# attenuverter3.net
KiCad netlist of a schematic drawn in EAGLE
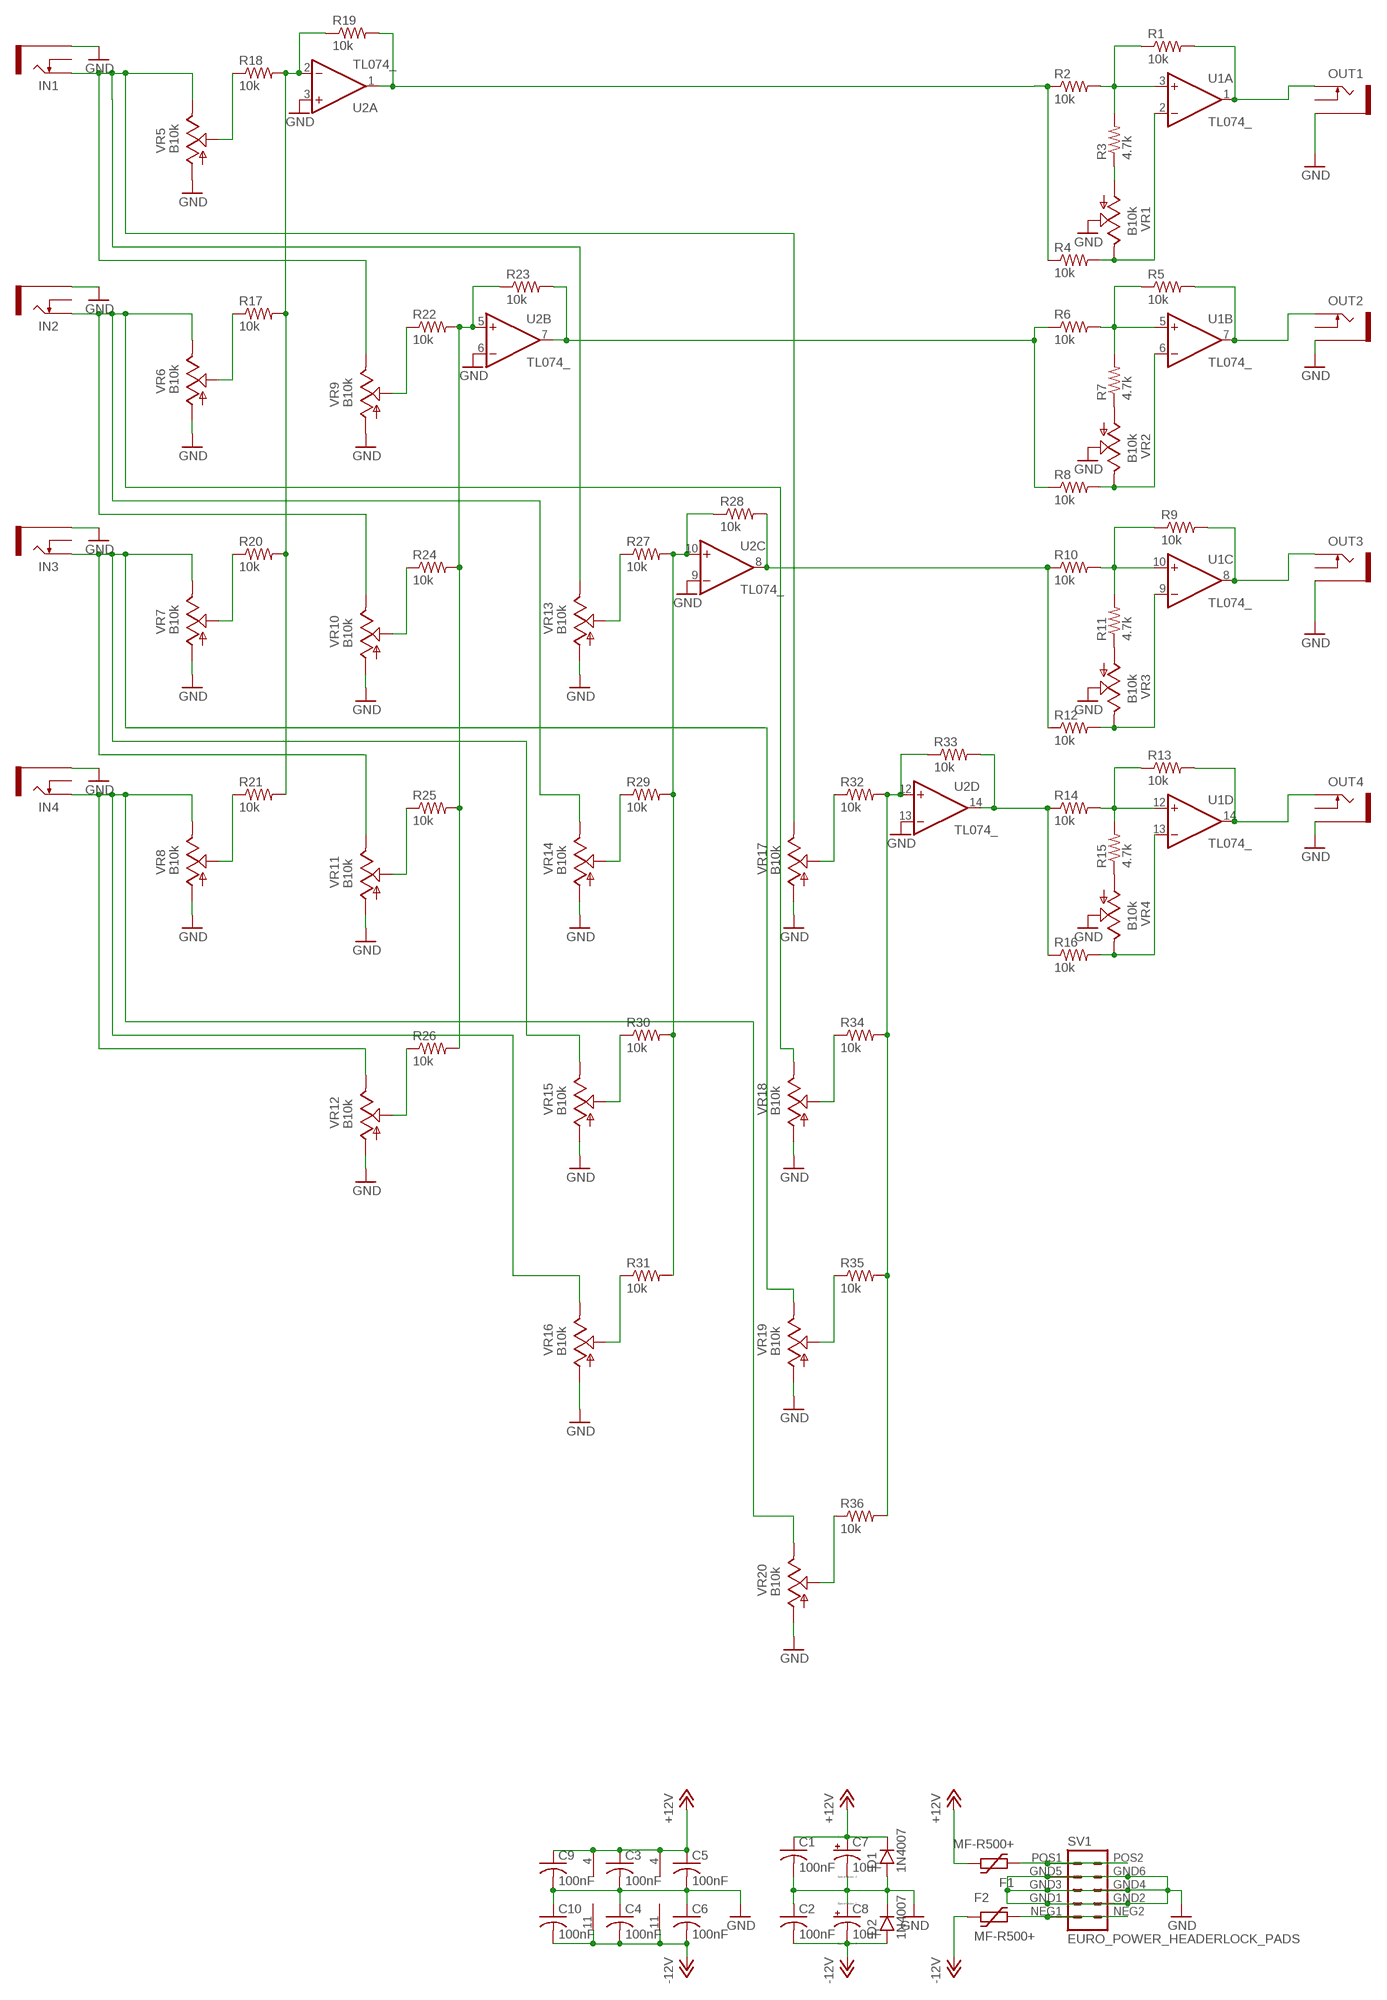
[diagram p0: schematic, sheet 1]

(export (version "E")
  (design (tool "Eeschema 10.0.6"))
  (components
    (comp (ref "C1")
      (value "100nF")
      (footprint "eagle-import:C050-055X075")
      (libsource (lib "eagle-import") (part "C-US050-055X075"))
    )
    (comp (ref "C2")
      (value "100nF")
      (footprint "eagle-import:C050-055X075")
      (libsource (lib "eagle-import") (part "C-US050-055X075"))
    )
    (comp (ref "C3")
      (value "100nF")
      (footprint "eagle-import:C050-055X075")
      (libsource (lib "eagle-import") (part "C-US050-055X075"))
    )
    (comp (ref "C4")
      (value "100nF")
      (footprint "eagle-import:C050-055X075")
      (libsource (lib "eagle-import") (part "C-US050-055X075"))
    )
    (comp (ref "C5")
      (value "100nF")
      (footprint "eagle-import:C050-055X075")
      (libsource (lib "eagle-import") (part "C-US050-055X075"))
    )
    (comp (ref "C6")
      (value "100nF")
      (footprint "eagle-import:C050-055X075")
      (libsource (lib "eagle-import") (part "C-US050-055X075"))
    )
    (comp (ref "C7")
      (value "10uF")
      (footprint "eagle-import:E2,5-6")
      (libsource (lib "eagle-import") (part "CPOL-USE2.5-6"))
    )
    (comp (ref "C8")
      (value "10uF")
      (footprint "eagle-import:E2,5-6")
      (libsource (lib "eagle-import") (part "CPOL-USE2.5-6"))
    )
    (comp (ref "C9")
      (value "100nF")
      (footprint "eagle-import:C050-055X075")
      (libsource (lib "eagle-import") (part "C-US050-055X075"))
    )
    (comp (ref "C10")
      (value "100nF")
      (footprint "eagle-import:C050-055X075")
      (libsource (lib "eagle-import") (part "C-US050-055X075"))
    )
    (comp (ref "D1")
      (value "1N4007")
      (footprint "eagle-import:DO41-4")
      (libsource (lib "eagle-import") (part "1N400X.4"))
    )
    (comp (ref "D2")
      (value "1N4007")
      (footprint "eagle-import:DO41-4")
      (libsource (lib "eagle-import") (part "1N400X.4"))
    )
    (comp (ref "F1")
      (value "MF-R500+")
      (footprint "eagle-import:BOURNS-MF-R")
      (libsource (lib "eagle-import") (part "MF-R500+"))
    )
    (comp (ref "F2")
      (value "MF-R500+")
      (footprint "eagle-import:BOURNS-MF-R")
      (libsource (lib "eagle-import") (part "MF-R500+"))
    )
    (comp (ref "IN1")
      (value "THONKICONNNEW")
      (footprint "eagle-import:WQP-PJ301M-12_JACK")
      (libsource (lib "eagle-import") (part "THONKICONNNEW"))
    )
    (comp (ref "IN2")
      (value "THONKICONNNEW")
      (footprint "eagle-import:WQP-PJ301M-12_JACK")
      (libsource (lib "eagle-import") (part "THONKICONNNEW"))
    )
    (comp (ref "IN3")
      (value "THONKICONNNEW")
      (footprint "eagle-import:WQP-PJ301M-12_JACK")
      (libsource (lib "eagle-import") (part "THONKICONNNEW"))
    )
    (comp (ref "IN4")
      (value "THONKICONNNEW")
      (footprint "eagle-import:WQP-PJ301M-12_JACK")
      (libsource (lib "eagle-import") (part "THONKICONNNEW"))
    )
    (comp (ref "OUT1")
      (value "THONKICONNNEW")
      (footprint "eagle-import:WQP-PJ301M-12_JACK")
      (libsource (lib "eagle-import") (part "THONKICONNNEW"))
    )
    (comp (ref "OUT2")
      (value "THONKICONNNEW")
      (footprint "eagle-import:WQP-PJ301M-12_JACK")
      (libsource (lib "eagle-import") (part "THONKICONNNEW"))
    )
    (comp (ref "OUT3")
      (value "THONKICONNNEW")
      (footprint "eagle-import:WQP-PJ301M-12_JACK")
      (libsource (lib "eagle-import") (part "THONKICONNNEW"))
    )
    (comp (ref "OUT4")
      (value "THONKICONNNEW")
      (footprint "eagle-import:WQP-PJ301M-12_JACK")
      (libsource (lib "eagle-import") (part "THONKICONNNEW"))
    )
    (comp (ref "R1")
      (value "10k")
      (footprint "eagle-import:0207_7")
      (libsource (lib "eagle-import") (part "R-US_0207/7"))
    )
    (comp (ref "R2")
      (value "10k")
      (footprint "eagle-import:0207_7")
      (libsource (lib "eagle-import") (part "R-US_0207/7"))
    )
    (comp (ref "R3")
      (value "4.7k")
      (footprint "eagle-import:0207_7")
      (libsource (lib "eagle-import") (part "R-US_0207/7"))
    )
    (comp (ref "R4")
      (value "10k")
      (footprint "eagle-import:0207_7")
      (libsource (lib "eagle-import") (part "R-US_0207/7"))
    )
    (comp (ref "R5")
      (value "10k")
      (footprint "eagle-import:0207_7")
      (libsource (lib "eagle-import") (part "R-US_0207/7"))
    )
    (comp (ref "R6")
      (value "10k")
      (footprint "eagle-import:0207_7")
      (libsource (lib "eagle-import") (part "R-US_0207/7"))
    )
    (comp (ref "R7")
      (value "4.7k")
      (footprint "eagle-import:0207_7")
      (libsource (lib "eagle-import") (part "R-US_0207/7"))
    )
    (comp (ref "R8")
      (value "10k")
      (footprint "eagle-import:0207_7")
      (libsource (lib "eagle-import") (part "R-US_0207/7"))
    )
    (comp (ref "R9")
      (value "10k")
      (footprint "eagle-import:0207_7")
      (libsource (lib "eagle-import") (part "R-US_0207/7"))
    )
    (comp (ref "R10")
      (value "10k")
      (footprint "eagle-import:0207_7")
      (libsource (lib "eagle-import") (part "R-US_0207/7"))
    )
    (comp (ref "R11")
      (value "4.7k")
      (footprint "eagle-import:0207_7")
      (libsource (lib "eagle-import") (part "R-US_0207/7"))
    )
    (comp (ref "R12")
      (value "10k")
      (footprint "eagle-import:0207_7")
      (libsource (lib "eagle-import") (part "R-US_0207/7"))
    )
    (comp (ref "R13")
      (value "10k")
      (footprint "eagle-import:0207_7")
      (libsource (lib "eagle-import") (part "R-US_0207/7"))
    )
    (comp (ref "R14")
      (value "10k")
      (footprint "eagle-import:0207_7")
      (libsource (lib "eagle-import") (part "R-US_0207/7"))
    )
    (comp (ref "R15")
      (value "4.7k")
      (footprint "eagle-import:0207_7")
      (libsource (lib "eagle-import") (part "R-US_0207/7"))
    )
    (comp (ref "R16")
      (value "10k")
      (footprint "eagle-import:0207_7")
      (libsource (lib "eagle-import") (part "R-US_0207/7"))
    )
    (comp (ref "R17")
      (value "10k")
      (footprint "eagle-import:0207_7")
      (libsource (lib "eagle-import") (part "R-US_0207/7"))
    )
    (comp (ref "R18")
      (value "10k")
      (footprint "eagle-import:0207_7")
      (libsource (lib "eagle-import") (part "R-US_0207/7"))
    )
    (comp (ref "R19")
      (value "10k")
      (footprint "eagle-import:0207_7")
      (libsource (lib "eagle-import") (part "R-US_0207/7"))
    )
    (comp (ref "R20")
      (value "10k")
      (footprint "eagle-import:0207_7")
      (libsource (lib "eagle-import") (part "R-US_0207/7"))
    )
    (comp (ref "R21")
      (value "10k")
      (footprint "eagle-import:0207_7")
      (libsource (lib "eagle-import") (part "R-US_0207/7"))
    )
    (comp (ref "R22")
      (value "10k")
      (footprint "eagle-import:0207_7")
      (libsource (lib "eagle-import") (part "R-US_0207/7"))
    )
    (comp (ref "R23")
      (value "10k")
      (footprint "eagle-import:0207_7")
      (libsource (lib "eagle-import") (part "R-US_0207/7"))
    )
    (comp (ref "R24")
      (value "10k")
      (footprint "eagle-import:0207_7")
      (libsource (lib "eagle-import") (part "R-US_0207/7"))
    )
    (comp (ref "R25")
      (value "10k")
      (footprint "eagle-import:0207_7")
      (libsource (lib "eagle-import") (part "R-US_0207/7"))
    )
    (comp (ref "R26")
      (value "10k")
      (footprint "eagle-import:0207_7")
      (libsource (lib "eagle-import") (part "R-US_0207/7"))
    )
    (comp (ref "R27")
      (value "10k")
      (footprint "eagle-import:0207_7")
      (libsource (lib "eagle-import") (part "R-US_0207/7"))
    )
    (comp (ref "R28")
      (value "10k")
      (footprint "eagle-import:0207_7")
      (libsource (lib "eagle-import") (part "R-US_0207/7"))
    )
    (comp (ref "R29")
      (value "10k")
      (footprint "eagle-import:0207_7")
      (libsource (lib "eagle-import") (part "R-US_0207/7"))
    )
    (comp (ref "R30")
      (value "10k")
      (footprint "eagle-import:0207_7")
      (libsource (lib "eagle-import") (part "R-US_0207/7"))
    )
    (comp (ref "R31")
      (value "10k")
      (footprint "eagle-import:0207_7")
      (libsource (lib "eagle-import") (part "R-US_0207/7"))
    )
    (comp (ref "R32")
      (value "10k")
      (footprint "eagle-import:0207_7")
      (libsource (lib "eagle-import") (part "R-US_0207/7"))
    )
    (comp (ref "R33")
      (value "10k")
      (footprint "eagle-import:0207_7")
      (libsource (lib "eagle-import") (part "R-US_0207/7"))
    )
    (comp (ref "R34")
      (value "10k")
      (footprint "eagle-import:0207_7")
      (libsource (lib "eagle-import") (part "R-US_0207/7"))
    )
    (comp (ref "R35")
      (value "10k")
      (footprint "eagle-import:0207_7")
      (libsource (lib "eagle-import") (part "R-US_0207/7"))
    )
    (comp (ref "R36")
      (value "10k")
      (footprint "eagle-import:0207_7")
      (libsource (lib "eagle-import") (part "R-US_0207/7"))
    )
    (comp (ref "SV1")
      (value "EURO_POWER_HEADERLOCK_PADS")
      (footprint "eagle-import:EURO_PWR_HEADER_LOCK")
      (libsource (lib "eagle-import") (part "EURO_POWER_HEADERLOCK_PADS"))
    )
    (comp (ref "U1")
      (value "TL074_")
      (footprint "eagle-import:DIL14")
      (libsource (lib "eagle-import") (part "TL074_"))
    )
    (comp (ref "U2")
      (value "TL074_")
      (footprint "eagle-import:DIL14")
      (libsource (lib "eagle-import") (part "TL074_"))
    )
    (comp (ref "VR1")
      (value "B10k")
      (footprint "eagle-import:9MM_SNAP-IN_POT")
      (libsource (lib "eagle-import") (part "9MM_SNAP-IN_POT_"))
    )
    (comp (ref "VR2")
      (value "B10k")
      (footprint "eagle-import:9MM_SNAP-IN_POT")
      (libsource (lib "eagle-import") (part "9MM_SNAP-IN_POT_"))
    )
    (comp (ref "VR3")
      (value "B10k")
      (footprint "eagle-import:9MM_SNAP-IN_POT")
      (libsource (lib "eagle-import") (part "9MM_SNAP-IN_POT_"))
    )
    (comp (ref "VR4")
      (value "B10k")
      (footprint "eagle-import:9MM_SNAP-IN_POT")
      (libsource (lib "eagle-import") (part "9MM_SNAP-IN_POT_"))
    )
    (comp (ref "VR5")
      (value "B10k")
      (footprint "eagle-import:9MM_SNAP-IN_POT")
      (libsource (lib "eagle-import") (part "9MM_SNAP-IN_POT_"))
    )
    (comp (ref "VR6")
      (value "B10k")
      (footprint "eagle-import:9MM_SNAP-IN_POT")
      (libsource (lib "eagle-import") (part "9MM_SNAP-IN_POT_"))
    )
    (comp (ref "VR7")
      (value "B10k")
      (footprint "eagle-import:9MM_SNAP-IN_POT")
      (libsource (lib "eagle-import") (part "9MM_SNAP-IN_POT_"))
    )
    (comp (ref "VR8")
      (value "B10k")
      (footprint "eagle-import:9MM_SNAP-IN_POT")
      (libsource (lib "eagle-import") (part "9MM_SNAP-IN_POT_"))
    )
    (comp (ref "VR9")
      (value "B10k")
      (footprint "eagle-import:9MM_SNAP-IN_POT")
      (libsource (lib "eagle-import") (part "9MM_SNAP-IN_POT_"))
    )
    (comp (ref "VR10")
      (value "B10k")
      (footprint "eagle-import:9MM_SNAP-IN_POT")
      (libsource (lib "eagle-import") (part "9MM_SNAP-IN_POT_"))
    )
    (comp (ref "VR11")
      (value "B10k")
      (footprint "eagle-import:9MM_SNAP-IN_POT")
      (libsource (lib "eagle-import") (part "9MM_SNAP-IN_POT_"))
    )
    (comp (ref "VR12")
      (value "B10k")
      (footprint "eagle-import:9MM_SNAP-IN_POT")
      (libsource (lib "eagle-import") (part "9MM_SNAP-IN_POT_"))
    )
    (comp (ref "VR13")
      (value "B10k")
      (footprint "eagle-import:9MM_SNAP-IN_POT")
      (libsource (lib "eagle-import") (part "9MM_SNAP-IN_POT_"))
    )
    (comp (ref "VR14")
      (value "B10k")
      (footprint "eagle-import:9MM_SNAP-IN_POT")
      (libsource (lib "eagle-import") (part "9MM_SNAP-IN_POT_"))
    )
    (comp (ref "VR15")
      (value "B10k")
      (footprint "eagle-import:9MM_SNAP-IN_POT")
      (libsource (lib "eagle-import") (part "9MM_SNAP-IN_POT_"))
    )
    (comp (ref "VR16")
      (value "B10k")
      (footprint "eagle-import:9MM_SNAP-IN_POT")
      (libsource (lib "eagle-import") (part "9MM_SNAP-IN_POT_"))
    )
    (comp (ref "VR17")
      (value "B10k")
      (footprint "eagle-import:9MM_SNAP-IN_POT")
      (libsource (lib "eagle-import") (part "9MM_SNAP-IN_POT_"))
    )
    (comp (ref "VR18")
      (value "B10k")
      (footprint "eagle-import:9MM_SNAP-IN_POT")
      (libsource (lib "eagle-import") (part "9MM_SNAP-IN_POT_"))
    )
    (comp (ref "VR19")
      (value "B10k")
      (footprint "eagle-import:9MM_SNAP-IN_POT")
      (libsource (lib "eagle-import") (part "9MM_SNAP-IN_POT_"))
    )
    (comp (ref "VR20")
      (value "B10k")
      (footprint "eagle-import:9MM_SNAP-IN_POT")
      (libsource (lib "eagle-import") (part "9MM_SNAP-IN_POT_"))
    )
  )
  (nets
    (net (code "1") (name "+12V") (class "Default")
      (node (ref "C1") (pin "1") (pinfunction "1_1") (pintype "passive"))
      (node (ref "C3") (pin "1") (pinfunction "1_1") (pintype "passive"))
      (node (ref "C5") (pin "1") (pinfunction "1_1") (pintype "passive"))
      (node (ref "C7") (pin "+") (pinfunction "+_+") (pintype "passive"))
      (node (ref "C9") (pin "1") (pinfunction "1_1") (pintype "passive"))
      (node (ref "D1") (pin "C") (pinfunction "C_C") (pintype "passive"))
      (node (ref "F1") (pin "P$2") (pinfunction "2_P$2") (pintype "passive"))
      (node (ref "U1") (pin "4") (pinfunction "V+_4") (pintype "power_in"))
      (node (ref "U2") (pin "4") (pinfunction "V+_4") (pintype "power_in"))
    )
    (net (code "2") (name "-12V") (class "Default")
      (node (ref "C10") (pin "2") (pinfunction "2_2") (pintype "passive"))
      (node (ref "C2") (pin "2") (pinfunction "2_2") (pintype "passive"))
      (node (ref "C4") (pin "2") (pinfunction "2_2") (pintype "passive"))
      (node (ref "C6") (pin "2") (pinfunction "2_2") (pintype "passive"))
      (node (ref "C8") (pin "-") (pinfunction "-_-") (pintype "passive"))
      (node (ref "D2") (pin "A") (pinfunction "A_A") (pintype "passive"))
      (node (ref "F2") (pin "P$1") (pinfunction "1_P$1") (pintype "passive"))
      (node (ref "U1") (pin "11") (pinfunction "V-_11") (pintype "power_in"))
      (node (ref "U2") (pin "11") (pinfunction "V-_11") (pintype "power_in"))
    )
    (net (code "3") (name "GND") (class "Default")
      (node (ref "C1") (pin "2") (pinfunction "2_2") (pintype "passive"))
      (node (ref "C10") (pin "1") (pinfunction "1_1") (pintype "passive"))
      (node (ref "C2") (pin "1") (pinfunction "1_1") (pintype "passive"))
      (node (ref "C3") (pin "2") (pinfunction "2_2") (pintype "passive"))
      (node (ref "C4") (pin "1") (pinfunction "1_1") (pintype "passive"))
      (node (ref "C5") (pin "2") (pinfunction "2_2") (pintype "passive"))
      (node (ref "C6") (pin "1") (pinfunction "1_1") (pintype "passive"))
      (node (ref "C7") (pin "-") (pinfunction "-_-") (pintype "passive"))
      (node (ref "C8") (pin "+") (pinfunction "+_+") (pintype "passive"))
      (node (ref "C9") (pin "2") (pinfunction "2_2") (pintype "passive"))
      (node (ref "D1") (pin "A") (pinfunction "A_A") (pintype "passive"))
      (node (ref "D2") (pin "C") (pinfunction "C_C") (pintype "passive"))
      (node (ref "IN1") (pin "P$3_SLEEVE") (pinfunction "SLEEVE_P$3_SLEEVE") (pintype "passive"))
      (node (ref "IN2") (pin "P$3_SLEEVE") (pinfunction "SLEEVE_P$3_SLEEVE") (pintype "passive"))
      (node (ref "IN3") (pin "P$3_SLEEVE") (pinfunction "SLEEVE_P$3_SLEEVE") (pintype "passive"))
      (node (ref "IN4") (pin "P$3_SLEEVE") (pinfunction "SLEEVE_P$3_SLEEVE") (pintype "passive"))
      (node (ref "OUT1") (pin "P$3_SLEEVE") (pinfunction "SLEEVE_P$3_SLEEVE") (pintype "passive"))
      (node (ref "OUT2") (pin "P$3_SLEEVE") (pinfunction "SLEEVE_P$3_SLEEVE") (pintype "passive"))
      (node (ref "OUT3") (pin "P$3_SLEEVE") (pinfunction "SLEEVE_P$3_SLEEVE") (pintype "passive"))
      (node (ref "OUT4") (pin "P$3_SLEEVE") (pinfunction "SLEEVE_P$3_SLEEVE") (pintype "passive"))
      (node (ref "SV1") (pin "GND1") (pinfunction "4_GND1") (pintype "passive"))
      (node (ref "SV1") (pin "GND2") (pinfunction "3_GND2") (pintype "passive"))
      (node (ref "SV1") (pin "GND3") (pinfunction "6_GND3") (pintype "passive"))
      (node (ref "SV1") (pin "GND4") (pinfunction "5_GND4") (pintype "passive"))
      (node (ref "SV1") (pin "GND5") (pinfunction "8_GND5") (pintype "passive"))
      (node (ref "SV1") (pin "GND6") (pinfunction "7_GND6") (pintype "passive"))
      (node (ref "U2") (pin "13") (pinfunction "-IN_13") (pintype "input"))
      (node (ref "U2") (pin "3") (pinfunction "+IN_3") (pintype "input"))
      (node (ref "U2") (pin "6") (pinfunction "-IN_6") (pintype "input"))
      (node (ref "U2") (pin "9") (pinfunction "-IN_9") (pintype "input"))
      (node (ref "VR1") (pin "2") (pinfunction "S_2") (pintype "passive"))
      (node (ref "VR10") (pin "1") (pinfunction "A_1") (pintype "passive"))
      (node (ref "VR11") (pin "1") (pinfunction "A_1") (pintype "passive"))
      (node (ref "VR12") (pin "1") (pinfunction "A_1") (pintype "passive"))
      (node (ref "VR13") (pin "1") (pinfunction "A_1") (pintype "passive"))
      (node (ref "VR14") (pin "1") (pinfunction "A_1") (pintype "passive"))
      (node (ref "VR15") (pin "1") (pinfunction "A_1") (pintype "passive"))
      (node (ref "VR16") (pin "1") (pinfunction "A_1") (pintype "passive"))
      (node (ref "VR17") (pin "1") (pinfunction "A_1") (pintype "passive"))
      (node (ref "VR18") (pin "1") (pinfunction "A_1") (pintype "passive"))
      (node (ref "VR19") (pin "1") (pinfunction "A_1") (pintype "passive"))
      (node (ref "VR2") (pin "2") (pinfunction "S_2") (pintype "passive"))
      (node (ref "VR20") (pin "1") (pinfunction "A_1") (pintype "passive"))
      (node (ref "VR3") (pin "2") (pinfunction "S_2") (pintype "passive"))
      (node (ref "VR4") (pin "2") (pinfunction "S_2") (pintype "passive"))
      (node (ref "VR5") (pin "1") (pinfunction "A_1") (pintype "passive"))
      (node (ref "VR6") (pin "1") (pinfunction "A_1") (pintype "passive"))
      (node (ref "VR7") (pin "1") (pinfunction "A_1") (pintype "passive"))
      (node (ref "VR8") (pin "1") (pinfunction "A_1") (pintype "passive"))
      (node (ref "VR9") (pin "1") (pinfunction "A_1") (pintype "passive"))
    )
    (net (code "4") (name "Net-(F1-1)") (class "Default")
      (node (ref "F1") (pin "P$1") (pinfunction "1_P$1") (pintype "passive"))
      (node (ref "SV1") (pin "POS1") (pinfunction "10_POS1") (pintype "passive"))
      (node (ref "SV1") (pin "POS2") (pinfunction "9_POS2") (pintype "passive"))
    )
    (net (code "5") (name "Net-(F2-2)") (class "Default")
      (node (ref "F2") (pin "P$2") (pinfunction "2_P$2") (pintype "passive"))
      (node (ref "SV1") (pin "NEG1") (pinfunction "2_NEG1") (pintype "passive"))
      (node (ref "SV1") (pin "NEG2") (pinfunction "1_NEG2") (pintype "passive"))
    )
    (net (code "6") (name "Net-(IN1-TIP)") (class "Default")
      (node (ref "IN1") (pin "P$1_TIP") (pinfunction "TIP_P$1_TIP") (pintype "passive"))
      (node (ref "VR13") (pin "3") (pinfunction "E_3") (pintype "passive"))
      (node (ref "VR17") (pin "3") (pinfunction "E_3") (pintype "passive"))
      (node (ref "VR5") (pin "3") (pinfunction "E_3") (pintype "passive"))
      (node (ref "VR9") (pin "3") (pinfunction "E_3") (pintype "passive"))
    )
    (net (code "7") (name "Net-(IN2-TIP)") (class "Default")
      (node (ref "IN2") (pin "P$1_TIP") (pinfunction "TIP_P$1_TIP") (pintype "passive"))
      (node (ref "VR10") (pin "3") (pinfunction "E_3") (pintype "passive"))
      (node (ref "VR14") (pin "3") (pinfunction "E_3") (pintype "passive"))
      (node (ref "VR18") (pin "3") (pinfunction "E_3") (pintype "passive"))
      (node (ref "VR6") (pin "3") (pinfunction "E_3") (pintype "passive"))
    )
    (net (code "8") (name "Net-(IN3-TIP)") (class "Default")
      (node (ref "IN3") (pin "P$1_TIP") (pinfunction "TIP_P$1_TIP") (pintype "passive"))
      (node (ref "VR11") (pin "3") (pinfunction "E_3") (pintype "passive"))
      (node (ref "VR15") (pin "3") (pinfunction "E_3") (pintype "passive"))
      (node (ref "VR19") (pin "3") (pinfunction "E_3") (pintype "passive"))
      (node (ref "VR7") (pin "3") (pinfunction "E_3") (pintype "passive"))
    )
    (net (code "9") (name "Net-(IN4-TIP)") (class "Default")
      (node (ref "IN4") (pin "P$1_TIP") (pinfunction "TIP_P$1_TIP") (pintype "passive"))
      (node (ref "VR12") (pin "3") (pinfunction "E_3") (pintype "passive"))
      (node (ref "VR16") (pin "3") (pinfunction "E_3") (pintype "passive"))
      (node (ref "VR20") (pin "3") (pinfunction "E_3") (pintype "passive"))
      (node (ref "VR8") (pin "3") (pinfunction "E_3") (pintype "passive"))
    )
    (net (code "10") (name "Net-(OUT1-TIP)") (class "Default")
      (node (ref "OUT1") (pin "P$1_TIP") (pinfunction "TIP_P$1_TIP") (pintype "passive"))
      (node (ref "R1") (pin "2") (pinfunction "2_2") (pintype "passive"))
      (node (ref "U1") (pin "1") (pinfunction "OUT_1") (pintype "output"))
    )
    (net (code "11") (name "Net-(OUT2-TIP)") (class "Default")
      (node (ref "OUT2") (pin "P$1_TIP") (pinfunction "TIP_P$1_TIP") (pintype "passive"))
      (node (ref "R5") (pin "2") (pinfunction "2_2") (pintype "passive"))
      (node (ref "U1") (pin "7") (pinfunction "OUT_7") (pintype "output"))
    )
    (net (code "12") (name "Net-(OUT3-TIP)") (class "Default")
      (node (ref "OUT3") (pin "P$1_TIP") (pinfunction "TIP_P$1_TIP") (pintype "passive"))
      (node (ref "R9") (pin "2") (pinfunction "2_2") (pintype "passive"))
      (node (ref "U1") (pin "8") (pinfunction "OUT_8") (pintype "output"))
    )
    (net (code "13") (name "Net-(OUT4-TIP)") (class "Default")
      (node (ref "OUT4") (pin "P$1_TIP") (pinfunction "TIP_P$1_TIP") (pintype "passive"))
      (node (ref "R13") (pin "2") (pinfunction "2_2") (pintype "passive"))
      (node (ref "U1") (pin "14") (pinfunction "OUT_14") (pintype "output"))
    )
    (net (code "14") (name "Net-(U1A-+IN)") (class "Default")
      (node (ref "R1") (pin "1") (pinfunction "1_1") (pintype "passive"))
      (node (ref "R2") (pin "2") (pinfunction "2_2") (pintype "passive"))
      (node (ref "R3") (pin "2") (pinfunction "2_2") (pintype "passive"))
      (node (ref "U1") (pin "3") (pinfunction "+IN_3") (pintype "input"))
    )
    (net (code "15") (name "Net-(U1A--IN)") (class "Default")
      (node (ref "R4") (pin "2") (pinfunction "2_2") (pintype "passive"))
      (node (ref "U1") (pin "2") (pinfunction "-IN_2") (pintype "input"))
      (node (ref "VR1") (pin "3") (pinfunction "E_3") (pintype "passive"))
    )
    (net (code "16") (name "Net-(U1B-+IN)") (class "Default")
      (node (ref "R5") (pin "1") (pinfunction "1_1") (pintype "passive"))
      (node (ref "R6") (pin "2") (pinfunction "2_2") (pintype "passive"))
      (node (ref "R7") (pin "2") (pinfunction "2_2") (pintype "passive"))
      (node (ref "U1") (pin "5") (pinfunction "+IN_5") (pintype "input"))
    )
    (net (code "17") (name "Net-(U1B--IN)") (class "Default")
      (node (ref "R8") (pin "2") (pinfunction "2_2") (pintype "passive"))
      (node (ref "U1") (pin "6") (pinfunction "-IN_6") (pintype "input"))
      (node (ref "VR2") (pin "3") (pinfunction "E_3") (pintype "passive"))
    )
    (net (code "18") (name "Net-(U1C-+IN)") (class "Default")
      (node (ref "R10") (pin "2") (pinfunction "2_2") (pintype "passive"))
      (node (ref "R11") (pin "2") (pinfunction "2_2") (pintype "passive"))
      (node (ref "R9") (pin "1") (pinfunction "1_1") (pintype "passive"))
      (node (ref "U1") (pin "10") (pinfunction "+IN_10") (pintype "input"))
    )
    (net (code "19") (name "Net-(U1C--IN)") (class "Default")
      (node (ref "R12") (pin "2") (pinfunction "2_2") (pintype "passive"))
      (node (ref "U1") (pin "9") (pinfunction "-IN_9") (pintype "input"))
      (node (ref "VR3") (pin "3") (pinfunction "E_3") (pintype "passive"))
    )
    (net (code "20") (name "Net-(U1D-+IN)") (class "Default")
      (node (ref "R13") (pin "1") (pinfunction "1_1") (pintype "passive"))
      (node (ref "R14") (pin "2") (pinfunction "2_2") (pintype "passive"))
      (node (ref "R15") (pin "2") (pinfunction "2_2") (pintype "passive"))
      (node (ref "U1") (pin "12") (pinfunction "+IN_12") (pintype "input"))
    )
    (net (code "21") (name "Net-(U1D--IN)") (class "Default")
      (node (ref "R16") (pin "2") (pinfunction "2_2") (pintype "passive"))
      (node (ref "U1") (pin "13") (pinfunction "-IN_13") (pintype "input"))
      (node (ref "VR4") (pin "3") (pinfunction "E_3") (pintype "passive"))
    )
    (net (code "22") (name "Net-(U2A--IN)") (class "Default")
      (node (ref "R17") (pin "2") (pinfunction "2_2") (pintype "passive"))
      (node (ref "R18") (pin "2") (pinfunction "2_2") (pintype "passive"))
      (node (ref "R19") (pin "1") (pinfunction "1_1") (pintype "passive"))
      (node (ref "R20") (pin "2") (pinfunction "2_2") (pintype "passive"))
      (node (ref "R21") (pin "2") (pinfunction "2_2") (pintype "passive"))
      (node (ref "U2") (pin "2") (pinfunction "-IN_2") (pintype "input"))
    )
    (net (code "23") (name "Net-(U2A-OUT)") (class "Default")
      (node (ref "R19") (pin "2") (pinfunction "2_2") (pintype "passive"))
      (node (ref "R2") (pin "1") (pinfunction "1_1") (pintype "passive"))
      (node (ref "R4") (pin "1") (pinfunction "1_1") (pintype "passive"))
      (node (ref "U2") (pin "1") (pinfunction "OUT_1") (pintype "output"))
    )
    (net (code "24") (name "Net-(U2B-+IN)") (class "Default")
      (node (ref "R22") (pin "2") (pinfunction "2_2") (pintype "passive"))
      (node (ref "R23") (pin "1") (pinfunction "1_1") (pintype "passive"))
      (node (ref "R24") (pin "2") (pinfunction "2_2") (pintype "passive"))
      (node (ref "R25") (pin "2") (pinfunction "2_2") (pintype "passive"))
      (node (ref "R26") (pin "2") (pinfunction "2_2") (pintype "passive"))
      (node (ref "U2") (pin "5") (pinfunction "+IN_5") (pintype "input"))
    )
    (net (code "25") (name "Net-(U2B-OUT)") (class "Default")
      (node (ref "R23") (pin "2") (pinfunction "2_2") (pintype "passive"))
      (node (ref "R6") (pin "1") (pinfunction "1_1") (pintype "passive"))
      (node (ref "R8") (pin "1") (pinfunction "1_1") (pintype "passive"))
      (node (ref "U2") (pin "7") (pinfunction "OUT_7") (pintype "output"))
    )
    (net (code "26") (name "Net-(U2C-+IN)") (class "Default")
      (node (ref "R27") (pin "2") (pinfunction "2_2") (pintype "passive"))
      (node (ref "R28") (pin "1") (pinfunction "1_1") (pintype "passive"))
      (node (ref "R29") (pin "2") (pinfunction "2_2") (pintype "passive"))
      (node (ref "R30") (pin "2") (pinfunction "2_2") (pintype "passive"))
      (node (ref "R31") (pin "2") (pinfunction "2_2") (pintype "passive"))
      (node (ref "U2") (pin "10") (pinfunction "+IN_10") (pintype "input"))
    )
    (net (code "27") (name "Net-(U2C-OUT)") (class "Default")
      (node (ref "R10") (pin "1") (pinfunction "1_1") (pintype "passive"))
      (node (ref "R12") (pin "1") (pinfunction "1_1") (pintype "passive"))
      (node (ref "R28") (pin "2") (pinfunction "2_2") (pintype "passive"))
      (node (ref "U2") (pin "8") (pinfunction "OUT_8") (pintype "output"))
    )
    (net (code "28") (name "Net-(U2D-+IN)") (class "Default")
      (node (ref "R32") (pin "2") (pinfunction "2_2") (pintype "passive"))
      (node (ref "R33") (pin "1") (pinfunction "1_1") (pintype "passive"))
      (node (ref "R34") (pin "2") (pinfunction "2_2") (pintype "passive"))
      (node (ref "R35") (pin "2") (pinfunction "2_2") (pintype "passive"))
      (node (ref "R36") (pin "2") (pinfunction "2_2") (pintype "passive"))
      (node (ref "U2") (pin "12") (pinfunction "+IN_12") (pintype "input"))
    )
    (net (code "29") (name "Net-(U2D-OUT)") (class "Default")
      (node (ref "R14") (pin "1") (pinfunction "1_1") (pintype "passive"))
      (node (ref "R16") (pin "1") (pinfunction "1_1") (pintype "passive"))
      (node (ref "R33") (pin "2") (pinfunction "2_2") (pintype "passive"))
      (node (ref "U2") (pin "14") (pinfunction "OUT_14") (pintype "output"))
    )
    (net (code "30") (name "Net-(VR1-A)") (class "Default")
      (node (ref "R3") (pin "1") (pinfunction "1_1") (pintype "passive"))
      (node (ref "VR1") (pin "1") (pinfunction "A_1") (pintype "passive"))
    )
    (net (code "31") (name "Net-(VR2-A)") (class "Default")
      (node (ref "R7") (pin "1") (pinfunction "1_1") (pintype "passive"))
      (node (ref "VR2") (pin "1") (pinfunction "A_1") (pintype "passive"))
    )
    (net (code "32") (name "Net-(VR3-A)") (class "Default")
      (node (ref "R11") (pin "1") (pinfunction "1_1") (pintype "passive"))
      (node (ref "VR3") (pin "1") (pinfunction "A_1") (pintype "passive"))
    )
    (net (code "33") (name "Net-(VR4-A)") (class "Default")
      (node (ref "R15") (pin "1") (pinfunction "1_1") (pintype "passive"))
      (node (ref "VR4") (pin "1") (pinfunction "A_1") (pintype "passive"))
    )
    (net (code "34") (name "Net-(VR5-S)") (class "Default")
      (node (ref "R18") (pin "1") (pinfunction "1_1") (pintype "passive"))
      (node (ref "VR5") (pin "2") (pinfunction "S_2") (pintype "passive"))
    )
    (net (code "35") (name "Net-(VR6-S)") (class "Default")
      (node (ref "R17") (pin "1") (pinfunction "1_1") (pintype "passive"))
      (node (ref "VR6") (pin "2") (pinfunction "S_2") (pintype "passive"))
    )
    (net (code "36") (name "Net-(VR7-S)") (class "Default")
      (node (ref "R20") (pin "1") (pinfunction "1_1") (pintype "passive"))
      (node (ref "VR7") (pin "2") (pinfunction "S_2") (pintype "passive"))
    )
    (net (code "37") (name "Net-(VR8-S)") (class "Default")
      (node (ref "R21") (pin "1") (pinfunction "1_1") (pintype "passive"))
      (node (ref "VR8") (pin "2") (pinfunction "S_2") (pintype "passive"))
    )
    (net (code "38") (name "Net-(VR9-S)") (class "Default")
      (node (ref "R22") (pin "1") (pinfunction "1_1") (pintype "passive"))
      (node (ref "VR9") (pin "2") (pinfunction "S_2") (pintype "passive"))
    )
    (net (code "39") (name "Net-(VR10-S)") (class "Default")
      (node (ref "R24") (pin "1") (pinfunction "1_1") (pintype "passive"))
      (node (ref "VR10") (pin "2") (pinfunction "S_2") (pintype "passive"))
    )
    (net (code "40") (name "Net-(VR11-S)") (class "Default")
      (node (ref "R25") (pin "1") (pinfunction "1_1") (pintype "passive"))
      (node (ref "VR11") (pin "2") (pinfunction "S_2") (pintype "passive"))
    )
    (net (code "41") (name "Net-(VR12-S)") (class "Default")
      (node (ref "R26") (pin "1") (pinfunction "1_1") (pintype "passive"))
      (node (ref "VR12") (pin "2") (pinfunction "S_2") (pintype "passive"))
    )
    (net (code "42") (name "Net-(VR13-S)") (class "Default")
      (node (ref "R27") (pin "1") (pinfunction "1_1") (pintype "passive"))
      (node (ref "VR13") (pin "2") (pinfunction "S_2") (pintype "passive"))
    )
    (net (code "43") (name "Net-(VR14-S)") (class "Default")
      (node (ref "R29") (pin "1") (pinfunction "1_1") (pintype "passive"))
      (node (ref "VR14") (pin "2") (pinfunction "S_2") (pintype "passive"))
    )
    (net (code "44") (name "Net-(VR15-S)") (class "Default")
      (node (ref "R30") (pin "1") (pinfunction "1_1") (pintype "passive"))
      (node (ref "VR15") (pin "2") (pinfunction "S_2") (pintype "passive"))
    )
    (net (code "45") (name "Net-(VR16-S)") (class "Default")
      (node (ref "R31") (pin "1") (pinfunction "1_1") (pintype "passive"))
      (node (ref "VR16") (pin "2") (pinfunction "S_2") (pintype "passive"))
    )
    (net (code "46") (name "Net-(VR17-S)") (class "Default")
      (node (ref "R32") (pin "1") (pinfunction "1_1") (pintype "passive"))
      (node (ref "VR17") (pin "2") (pinfunction "S_2") (pintype "passive"))
    )
    (net (code "47") (name "Net-(VR18-S)") (class "Default")
      (node (ref "R34") (pin "1") (pinfunction "1_1") (pintype "passive"))
      (node (ref "VR18") (pin "2") (pinfunction "S_2") (pintype "passive"))
    )
    (net (code "48") (name "Net-(VR19-S)") (class "Default")
      (node (ref "R35") (pin "1") (pinfunction "1_1") (pintype "passive"))
      (node (ref "VR19") (pin "2") (pinfunction "S_2") (pintype "passive"))
    )
    (net (code "49") (name "Net-(VR20-S)") (class "Default")
      (node (ref "R36") (pin "1") (pinfunction "1_1") (pintype "passive"))
      (node (ref "VR20") (pin "2") (pinfunction "S_2") (pintype "passive"))
    )
    (net (code "50") (name "unconnected-(IN1-SWITCH-PadP$2_SWITCH)") (class "Default")
      (node (ref "IN1") (pin "P$2_SWITCH") (pinfunction "SWITCH_P$2_SWITCH") (pintype "passive"))
    )
    (net (code "51") (name "unconnected-(IN2-SWITCH-PadP$2_SWITCH)") (class "Default")
      (node (ref "IN2") (pin "P$2_SWITCH") (pinfunction "SWITCH_P$2_SWITCH") (pintype "passive"))
    )
    (net (code "52") (name "unconnected-(IN3-SWITCH-PadP$2_SWITCH)") (class "Default")
      (node (ref "IN3") (pin "P$2_SWITCH") (pinfunction "SWITCH_P$2_SWITCH") (pintype "passive"))
    )
    (net (code "53") (name "unconnected-(IN4-SWITCH-PadP$2_SWITCH)") (class "Default")
      (node (ref "IN4") (pin "P$2_SWITCH") (pinfunction "SWITCH_P$2_SWITCH") (pintype "passive"))
    )
    (net (code "54") (name "unconnected-(OUT1-SWITCH-PadP$2_SWITCH)") (class "Default")
      (node (ref "OUT1") (pin "P$2_SWITCH") (pinfunction "SWITCH_P$2_SWITCH") (pintype "passive"))
    )
    (net (code "55") (name "unconnected-(OUT2-SWITCH-PadP$2_SWITCH)") (class "Default")
      (node (ref "OUT2") (pin "P$2_SWITCH") (pinfunction "SWITCH_P$2_SWITCH") (pintype "passive"))
    )
    (net (code "56") (name "unconnected-(OUT3-SWITCH-PadP$2_SWITCH)") (class "Default")
      (node (ref "OUT3") (pin "P$2_SWITCH") (pinfunction "SWITCH_P$2_SWITCH") (pintype "passive"))
    )
    (net (code "57") (name "unconnected-(OUT4-SWITCH-PadP$2_SWITCH)") (class "Default")
      (node (ref "OUT4") (pin "P$2_SWITCH") (pinfunction "SWITCH_P$2_SWITCH") (pintype "passive"))
    )
  )
)
